# 11_-_Wireless_-_CAN.net
KiCad netlist of a schematic drawn in Altium Designer
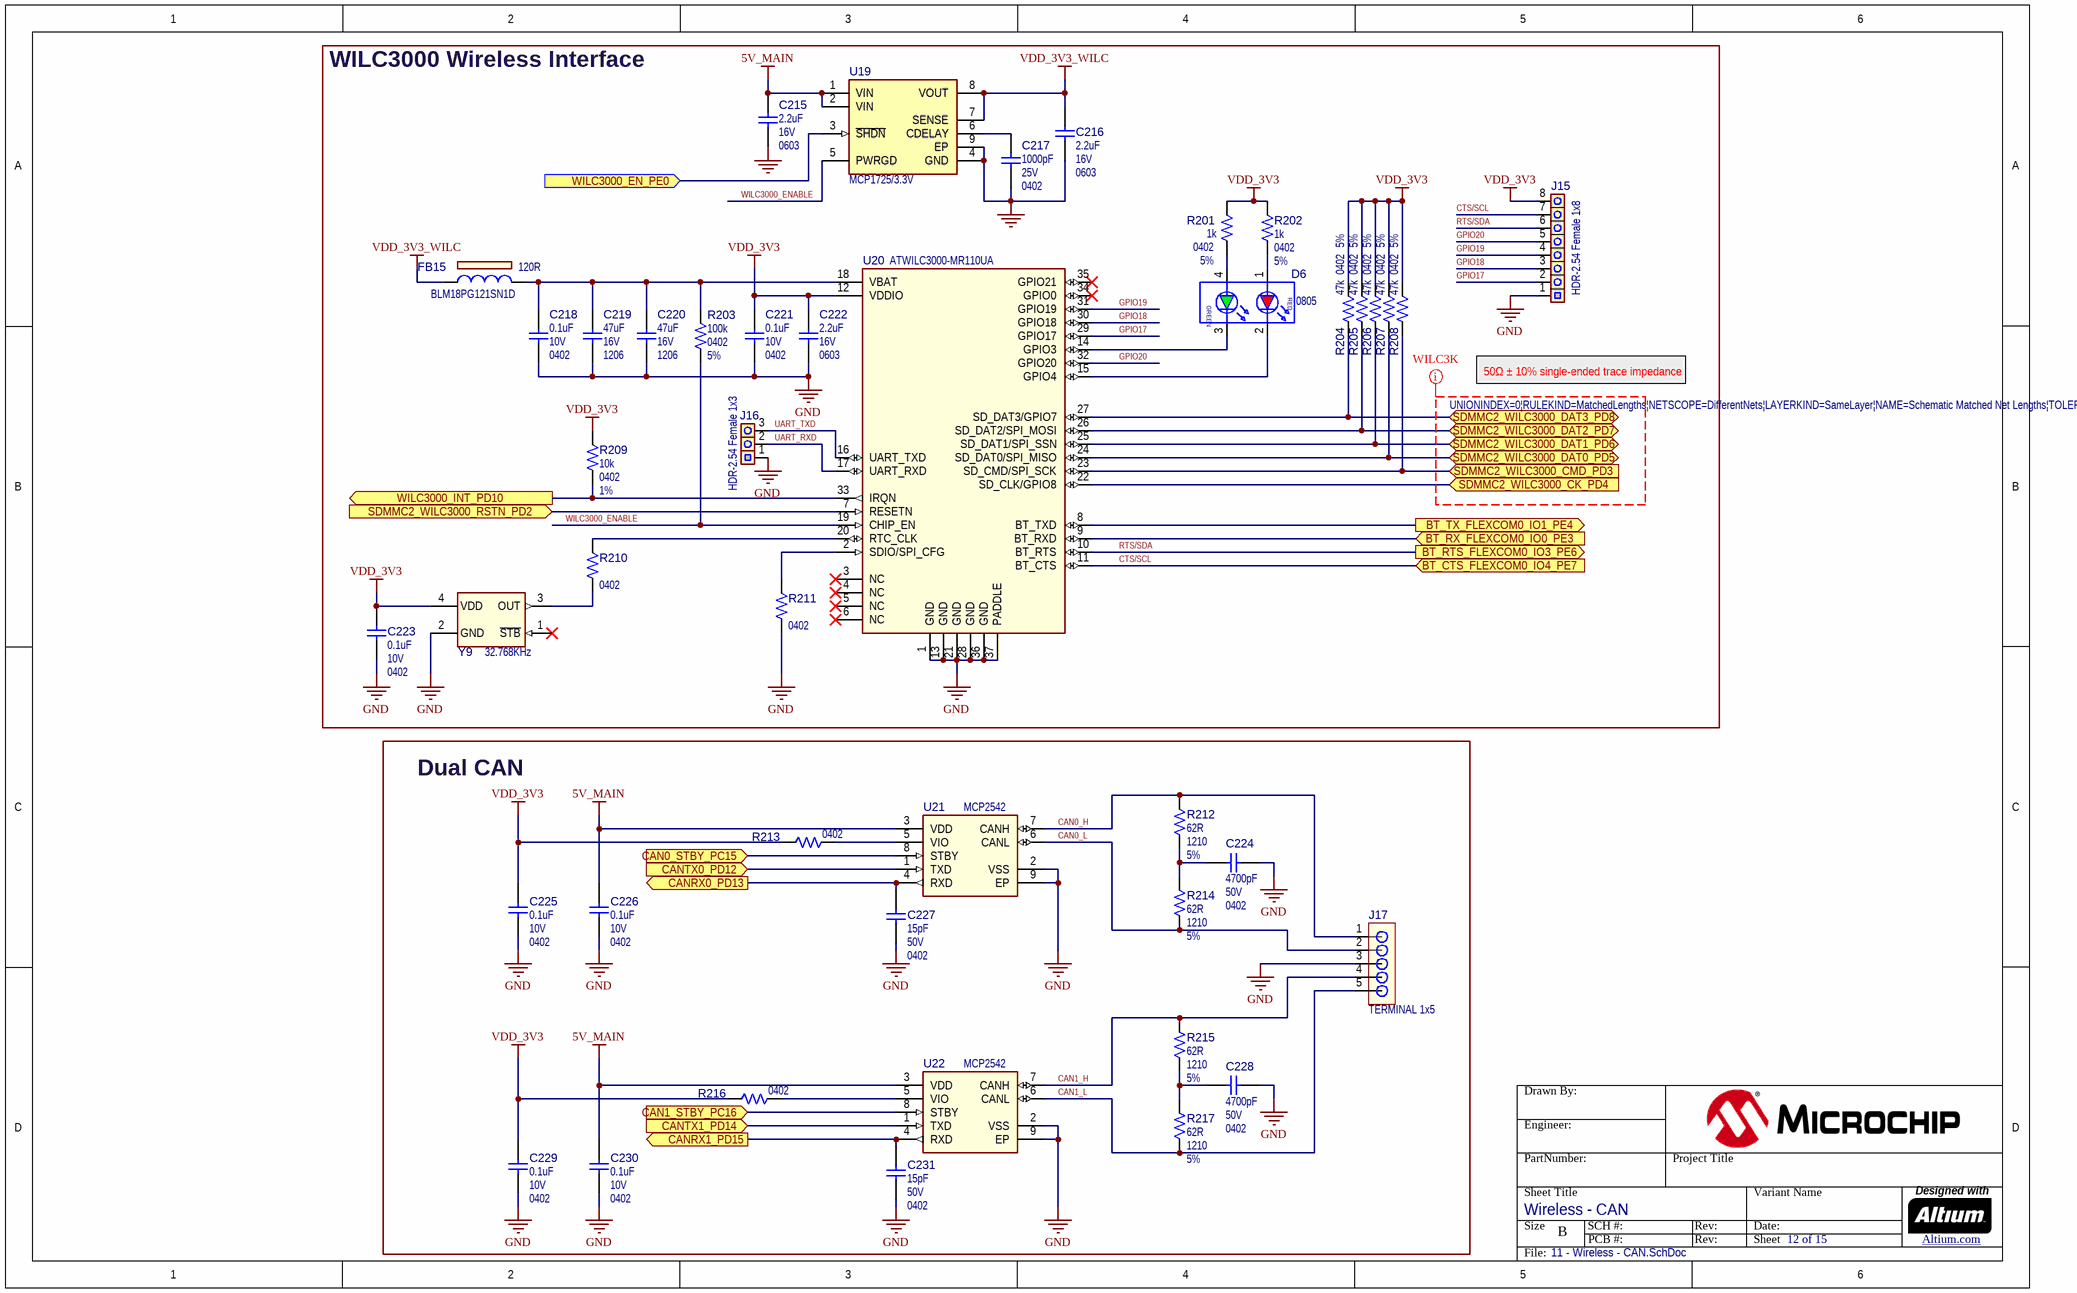
[diagram p0: 11 - Wireless - CAN.SchDoc]

(export (version "E")
  (design (tool "Eeschema 10.0.6"))
  (components
    (comp (ref "C215")
      (value "2.2uF")
      (footprint "CAP_C_0603")
      (description "Capacitor")
      (fields
        (field (name "VOLTAGE") "16V")
        (field (name "PACKAGE") "0603")
        (field (name "TOLERANCE") "10%")
        (field (name "Comment") "Capacitor NP")
      )
      (libsource (lib "MCHP-CDB") (part "Capacitor NP"))
    )
    (comp (ref "C216")
      (value "2.2uF")
      (footprint "CAP_C_0603")
      (description "Capacitor")
      (fields
        (field (name "VOLTAGE") "16V")
        (field (name "PACKAGE") "0603")
        (field (name "TOLERANCE") "10%")
        (field (name "Comment") "Capacitor NP")
      )
      (libsource (lib "MCHP-CDB") (part "Capacitor NP"))
    )
    (comp (ref "C217")
      (value "1000pF")
      (footprint "CAP_C_0402")
      (fields
        (field (name "VOLTAGE") "25V")
        (field (name "PACKAGE") "0402")
        (field (name "TOLERANCE") "10%")
        (field (name "Comment") "Capacitor NP")
        (field (name "OWNER") "Dragos Danaila")
      )
      (libsource (lib "") (part "Capacitor NP_1"))
    )
    (comp (ref "C218")
      (value "0.1uF")
      (footprint "CAP_C_0402")
      (description "Capacitor")
      (fields
        (field (name "VOLTAGE") "10V")
        (field (name "PACKAGE") "0402")
        (field (name "TOLERANCE") "10%")
        (field (name "Comment") "Capacitor NP")
        (field (name "OWNER") "Tad Ahlvers")
      )
      (libsource (lib "MCHP-CDB") (part "Capacitor NP"))
    )
    (comp (ref "C219")
      (value "47uF")
      (footprint "CAP_C_1206")
      (description "Capacitor")
      (fields
        (field (name "VOLTAGE") "16V")
        (field (name "PACKAGE") "1206")
        (field (name "TOLERANCE") "20%")
        (field (name "Comment") "Capacitor NP")
        (field (name "OWNER") "Bogdan Popescu")
      )
      (libsource (lib "MCHP-CDB") (part "Capacitor NP"))
    )
    (comp (ref "C220")
      (value "47uF")
      (footprint "CAP_C_1206")
      (description "Capacitor")
      (fields
        (field (name "VOLTAGE") "16V")
        (field (name "PACKAGE") "1206")
        (field (name "TOLERANCE") "20%")
        (field (name "Comment") "Capacitor NP")
        (field (name "OWNER") "Bogdan Popescu")
      )
      (libsource (lib "MCHP-CDB") (part "Capacitor NP"))
    )
    (comp (ref "C221")
      (value "0.1uF")
      (footprint "CAP_C_0402")
      (description "Capacitor")
      (fields
        (field (name "VOLTAGE") "10V")
        (field (name "PACKAGE") "0402")
        (field (name "TOLERANCE") "10%")
        (field (name "Comment") "Capacitor NP")
        (field (name "OWNER") "Tad Ahlvers")
      )
      (libsource (lib "MCHP-CDB") (part "Capacitor NP"))
    )
    (comp (ref "C222")
      (value "2.2uF")
      (footprint "CAP_C_0603")
      (description "Capacitor")
      (fields
        (field (name "VOLTAGE") "16V")
        (field (name "PACKAGE") "0603")
        (field (name "TOLERANCE") "10%")
        (field (name "Comment") "Capacitor NP")
      )
      (libsource (lib "MCHP-CDB") (part "Capacitor NP"))
    )
    (comp (ref "C223")
      (value "0.1uF")
      (footprint "CAP_C_0402")
      (description "Capacitor")
      (fields
        (field (name "VOLTAGE") "10V")
        (field (name "PACKAGE") "0402")
        (field (name "TOLERANCE") "10%")
        (field (name "Comment") "Capacitor NP")
        (field (name "OWNER") "Tad Ahlvers")
      )
      (libsource (lib "MCHP-CDB") (part "Capacitor NP"))
    )
    (comp (ref "C224")
      (value "4700pF")
      (footprint "CAP_C_0402")
      (description "Capacitor")
      (fields
        (field (name "VOLTAGE") "50V")
        (field (name "PACKAGE") "0402")
        (field (name "TOLERANCE") "10%")
        (field (name "Comment") "Capacitor NP")
        (field (name "OWNER") "Gabor Bihari")
      )
      (libsource (lib "MCHP-CDB") (part "Capacitor NP"))
    )
    (comp (ref "C225")
      (value "0.1uF")
      (footprint "CAP_C_0402")
      (description "Capacitor")
      (fields
        (field (name "VOLTAGE") "10V")
        (field (name "PACKAGE") "0402")
        (field (name "TOLERANCE") "10%")
        (field (name "Comment") "Capacitor NP")
        (field (name "OWNER") "Tad Ahlvers")
      )
      (libsource (lib "MCHP-CDB") (part "Capacitor NP"))
    )
    (comp (ref "C226")
      (value "0.1uF")
      (footprint "CAP_C_0402")
      (description "Capacitor")
      (fields
        (field (name "VOLTAGE") "10V")
        (field (name "PACKAGE") "0402")
        (field (name "TOLERANCE") "10%")
        (field (name "Comment") "Capacitor NP")
        (field (name "OWNER") "Tad Ahlvers")
      )
      (libsource (lib "MCHP-CDB") (part "Capacitor NP"))
    )
    (comp (ref "C227")
      (value "15pF")
      (footprint "CAP_C_0402")
      (fields
        (field (name "VOLTAGE") "50V")
        (field (name "PACKAGE") "0402")
        (field (name "TOLERANCE") "5%")
        (field (name "Comment") "Capacitor NP")
        (field (name "OWNER") "Dragos Danaila")
      )
      (libsource (lib "") (part "Capacitor NP_1"))
    )
    (comp (ref "C228")
      (value "4700pF")
      (footprint "CAP_C_0402")
      (description "Capacitor")
      (fields
        (field (name "VOLTAGE") "50V")
        (field (name "PACKAGE") "0402")
        (field (name "TOLERANCE") "10%")
        (field (name "Comment") "Capacitor NP")
        (field (name "OWNER") "Gabor Bihari")
      )
      (libsource (lib "MCHP-CDB") (part "Capacitor NP"))
    )
    (comp (ref "C229")
      (value "0.1uF")
      (footprint "CAP_C_0402")
      (description "Capacitor")
      (fields
        (field (name "VOLTAGE") "10V")
        (field (name "PACKAGE") "0402")
        (field (name "TOLERANCE") "10%")
        (field (name "Comment") "Capacitor NP")
        (field (name "OWNER") "Tad Ahlvers")
      )
      (libsource (lib "MCHP-CDB") (part "Capacitor NP"))
    )
    (comp (ref "C230")
      (value "0.1uF")
      (footprint "CAP_C_0402")
      (description "Capacitor")
      (fields
        (field (name "VOLTAGE") "10V")
        (field (name "PACKAGE") "0402")
        (field (name "TOLERANCE") "10%")
        (field (name "Comment") "Capacitor NP")
        (field (name "OWNER") "Tad Ahlvers")
      )
      (libsource (lib "MCHP-CDB") (part "Capacitor NP"))
    )
    (comp (ref "C231")
      (value "15pF")
      (footprint "CAP_C_0402")
      (fields
        (field (name "VOLTAGE") "50V")
        (field (name "PACKAGE") "0402")
        (field (name "TOLERANCE") "5%")
        (field (name "Comment") "Capacitor NP")
        (field (name "OWNER") "Dragos Danaila")
      )
      (libsource (lib "") (part "Capacitor NP_1"))
    )
    (comp (ref "D6")
      (value "LED DUAL 4 pin")
      (footprint "LED_DUAL_SMD_2x1.25mm")
      (description "LED")
      (fields
        (field (name "PACKAGE") "0805")
        (field (name "POWER") "75mW")
        (field (name "OWNER") "Bogdan P (M91398)")
      )
      (libsource (lib "MCHP-CDB") (part "LED DUAL 4 pin"))
    )
    (comp (ref "FB15")
      (value "120R")
      (footprint "IND_C_0603")
      (fields
        (field (name "MANUFACTURER PART NUMBER 1") "BLM18PG121SN1D")
        (field (name "Comment") "Ferrite Bead")
        (field (name "OWNER") "Petnarong Chaijaroong")
      )
      (libsource (lib "MCHP-CDB") (part "Ferrite Bead"))
    )
    (comp (ref "J15")
      (value "HDR-2.54 Female 1x8")
      (footprint "HDR_F_2.54_1X8")
      (description "CON HDR-2.54 Female 1x8 Gold TH")
      (fields (field (name "Comment") "Header 1x8") (field (name "OWNER") "Jamus Griego"))
      (libsource (lib "MCHP-CDB") (part "Header 1x8"))
    )
    (comp (ref "J16")
      (value "HDR-2.54 Female 1x3")
      (footprint "HDR_F_2.54_1x3")
      (fields (field (name "Comment") "Header 1x3") (field (name "OWNER") "Md Khan"))
      (libsource (lib "MCHP-CDB") (part "Header 1x3"))
    )
    (comp (ref "J17")
      (value "TERMINAL 1x5")
      (footprint "CON_TERMINAL_3.81_1x5_TH_RA_PHO_1727049")
      (fields
        (field (name "VOLTAGE") "300")
        (field (name "Comment") "Header 1x5")
        (field (name "OWNER") "Ciprian Abramov")
      )
      (libsource (lib "MCHP-CDB") (part "CON TERM BLK 1x5 TH Mount"))
    )
    (comp (ref "R201")
      (value "1k")
      (footprint "RES_C_0402")
      (description "Resistor")
      (fields
        (field (name "PACKAGE") "0402")
        (field (name "TOLERANCE") "5%")
        (field (name "VOLTAGE") "50V")
        (field (name "POWER") "1/16W")
        (field (name "OWNER") "Tad Ahlvers")
      )
      (libsource (lib "MCHP-CDB") (part "Resistor"))
    )
    (comp (ref "R202")
      (value "1k")
      (footprint "RES_C_0402")
      (description "Resistor")
      (fields
        (field (name "PACKAGE") "0402")
        (field (name "TOLERANCE") "5%")
        (field (name "VOLTAGE") "50V")
        (field (name "POWER") "1/16W")
        (field (name "OWNER") "Tad Ahlvers")
      )
      (libsource (lib "MCHP-CDB") (part "Resistor"))
    )
    (comp (ref "R203")
      (value "100k")
      (footprint "RES_C_0402")
      (description "Resistor")
      (fields
        (field (name "PACKAGE") "0402")
        (field (name "TOLERANCE") "5%")
        (field (name "POWER") "1/10W")
        (field (name "VOLTAGE") "50V")
      )
      (libsource (lib "MCHP-CDB") (part "Resistor"))
    )
    (comp (ref "R204")
      (value "47k")
      (footprint "RES_C_0402")
      (description "Resistor")
      (fields
        (field (name "PACKAGE") "0402")
        (field (name "TOLERANCE") "5%")
        (field (name "POWER") "1/10W")
        (field (name "VOLTAGE") "50V")
        (field (name "OWNER") "Tad Ahlvers")
      )
      (libsource (lib "MCHP-CDB") (part "Resistor"))
    )
    (comp (ref "R205")
      (value "47k")
      (footprint "RES_C_0402")
      (description "Resistor")
      (fields
        (field (name "PACKAGE") "0402")
        (field (name "TOLERANCE") "5%")
        (field (name "POWER") "1/10W")
        (field (name "VOLTAGE") "50V")
        (field (name "OWNER") "Tad Ahlvers")
      )
      (libsource (lib "MCHP-CDB") (part "Resistor"))
    )
    (comp (ref "R206")
      (value "47k")
      (footprint "RES_C_0402")
      (description "Resistor")
      (fields
        (field (name "PACKAGE") "0402")
        (field (name "TOLERANCE") "5%")
        (field (name "POWER") "1/10W")
        (field (name "VOLTAGE") "50V")
        (field (name "OWNER") "Tad Ahlvers")
      )
      (libsource (lib "MCHP-CDB") (part "Resistor"))
    )
    (comp (ref "R207")
      (value "47k")
      (footprint "RES_C_0402")
      (description "Resistor")
      (fields
        (field (name "PACKAGE") "0402")
        (field (name "TOLERANCE") "5%")
        (field (name "POWER") "1/10W")
        (field (name "VOLTAGE") "50V")
        (field (name "OWNER") "Tad Ahlvers")
      )
      (libsource (lib "MCHP-CDB") (part "Resistor"))
    )
    (comp (ref "R208")
      (value "47k")
      (footprint "RES_C_0402")
      (description "Resistor")
      (fields
        (field (name "PACKAGE") "0402")
        (field (name "TOLERANCE") "5%")
        (field (name "POWER") "1/10W")
        (field (name "VOLTAGE") "50V")
        (field (name "OWNER") "Tad Ahlvers")
      )
      (libsource (lib "MCHP-CDB") (part "Resistor"))
    )
    (comp (ref "R209")
      (value "10k")
      (footprint "RES_C_0402")
      (description "Resistor")
      (fields
        (field (name "PACKAGE") "0402")
        (field (name "TOLERANCE") "1%")
        (field (name "VOLTAGE") "50V")
        (field (name "POWER") "1/10W")
        (field (name "OWNER") "Brent Lanphear")
      )
      (libsource (lib "MCHP-CDB") (part "Resistor"))
    )
    (comp (ref "R210")
      (value "Resistor")
      (footprint "RES_C_0402")
      (fields
        (field (name "PACKAGE") "0402")
        (field (name "POWER") "1/16W")
        (field (name "VOLTAGE") "50V")
        (field (name "OWNER") "Dragos Danaila")
      )
      (libsource (lib "MCHP-CDB") (part "Resistor"))
    )
    (comp (ref "R211")
      (value "Resistor")
      (footprint "RES_C_0402")
      (fields
        (field (name "PACKAGE") "0402")
        (field (name "POWER") "1/16W")
        (field (name "VOLTAGE") "50V")
        (field (name "OWNER") "Dragos Danaila")
      )
      (libsource (lib "MCHP-CDB") (part "Resistor"))
    )
    (comp (ref "R212")
      (value "62R")
      (footprint "RES_C_1210")
      (description "Resistor")
      (fields
        (field (name "PACKAGE") "1210")
        (field (name "TOLERANCE") "5%")
        (field (name "VOLTAGE") "200V")
        (field (name "POWER") "1/2W")
        (field (name "OWNER") "Dragos Danaila")
      )
      (libsource (lib "MCHP-CDB") (part "Resistor"))
    )
    (comp (ref "R213")
      (value "Resistor")
      (footprint "RES_C_0402")
      (fields
        (field (name "PACKAGE") "0402")
        (field (name "POWER") "1/16W")
        (field (name "VOLTAGE") "50V")
        (field (name "OWNER") "Dragos Danaila")
      )
      (libsource (lib "MCHP-CDB") (part "Resistor"))
    )
    (comp (ref "R214")
      (value "62R")
      (footprint "RES_C_1210")
      (description "Resistor")
      (fields
        (field (name "PACKAGE") "1210")
        (field (name "TOLERANCE") "5%")
        (field (name "VOLTAGE") "200V")
        (field (name "POWER") "1/2W")
        (field (name "OWNER") "Dragos Danaila")
      )
      (libsource (lib "MCHP-CDB") (part "Resistor"))
    )
    (comp (ref "R215")
      (value "62R")
      (footprint "RES_C_1210")
      (description "Resistor")
      (fields
        (field (name "PACKAGE") "1210")
        (field (name "TOLERANCE") "5%")
        (field (name "VOLTAGE") "200V")
        (field (name "POWER") "1/2W")
        (field (name "OWNER") "Dragos Danaila")
      )
      (libsource (lib "MCHP-CDB") (part "Resistor"))
    )
    (comp (ref "R216")
      (value "Resistor")
      (footprint "RES_C_0402")
      (fields
        (field (name "PACKAGE") "0402")
        (field (name "POWER") "1/16W")
        (field (name "VOLTAGE") "50V")
        (field (name "OWNER") "Dragos Danaila")
      )
      (libsource (lib "MCHP-CDB") (part "Resistor"))
    )
    (comp (ref "R217")
      (value "62R")
      (footprint "RES_C_1210")
      (description "Resistor")
      (fields
        (field (name "PACKAGE") "1210")
        (field (name "TOLERANCE") "5%")
        (field (name "VOLTAGE") "200V")
        (field (name "POWER") "1/2W")
        (field (name "OWNER") "Dragos Danaila")
      )
      (libsource (lib "MCHP-CDB") (part "Resistor"))
    )
    (comp (ref "U19")
      (value "MCP1725/3.3V")
      (footprint "DFN-8_2x3")
      (description "LDO")
      (fields (field (name "Comment") "MCP172X FIX DFN-8"))
      (libsource (lib "MCHP-CDB") (part "MCP172X FIX DFN-8"))
    )
    (comp (ref "U20")
      (value "ATWILC3000-MR110UA")
      (footprint "MODULE ATWILC3000-MR110CA")
      (fields (field (name "Comment") "MODULE ATWILC3000-MR110CA") (field (name "OWNER") "Ilie Galan"))
      (libsource (lib "MCHP-CDB") (part "MODULE ATWILC3000-MR110CA"))
    )
    (comp (ref "U21")
      (value "MCP2542")
      (footprint "DFN-8_3x3_EP2.4X1.55")
      (fields (field (name "Comment") "MCP2542 DFN-8") (field (name "OWNER") "Ilie Galan"))
      (libsource (lib "MCHP-CDB") (part "MCP2542 DFN-8"))
    )
    (comp (ref "U22")
      (value "MCP2542")
      (footprint "DFN-8_3x3_EP2.4X1.55")
      (fields (field (name "Comment") "MCP2542 DFN-8") (field (name "OWNER") "Ilie Galan"))
      (libsource (lib "MCHP-CDB") (part "MCP2542 DFN-8"))
    )
    (comp (ref "Y9")
      (value "32.768KHz")
      (footprint "DFN-4_2x1.6")
      (fields (field (name "Comment") "DSC60xx DFN-4_LGA-4") (field (name "OWNER") "Ciprian Abramov"))
      (libsource (lib "MCHP-CDB") (part "DSC60xx DFN-4_LGA-4"))
    )
  )
  (nets
    (net (code "1") (name "/BT_RX_FLEXCOM0_IO0_PE3") (class "Default")
      (node (ref "U20") (pin "9") (pinfunction "BT_RXD_9") (pintype "bidirectional"))
    )
    (net (code "2") (name "/BT_TX_FLEXCOM0_IO1_PE4") (class "Default")
      (node (ref "U20") (pin "8") (pinfunction "BT_TXD_8") (pintype "bidirectional"))
    )
    (net (code "3") (name "/CAN0_H") (class "Default")
      (node (ref "J17") (pin "1") (pinfunction "1_1") (pintype "passive"))
      (node (ref "R212") (pin "2") (pinfunction "2_2") (pintype "passive"))
      (node (ref "U21") (pin "7") (pinfunction "CANH_7") (pintype "bidirectional"))
    )
    (net (code "4") (name "/CAN0_L") (class "Default")
      (node (ref "J17") (pin "2") (pinfunction "2_2") (pintype "passive"))
      (node (ref "R214") (pin "1") (pinfunction "1_1") (pintype "passive"))
      (node (ref "U21") (pin "6") (pinfunction "CANL_6") (pintype "bidirectional"))
    )
    (net (code "5") (name "/CAN0_STBY_PC15") (class "Default")
      (node (ref "U21") (pin "8") (pinfunction "STBY_8") (pintype "input"))
    )
    (net (code "6") (name "/CAN1_H") (class "Default")
      (node (ref "J17") (pin "4") (pinfunction "4_4") (pintype "passive"))
      (node (ref "R215") (pin "2") (pinfunction "2_2") (pintype "passive"))
      (node (ref "U22") (pin "7") (pinfunction "CANH_7") (pintype "bidirectional"))
    )
    (net (code "7") (name "/CAN1_L") (class "Default")
      (node (ref "J17") (pin "5") (pinfunction "5_5") (pintype "passive"))
      (node (ref "R217") (pin "1") (pinfunction "1_1") (pintype "passive"))
      (node (ref "U22") (pin "6") (pinfunction "CANL_6") (pintype "bidirectional"))
    )
    (net (code "8") (name "/CAN1_STBY_PC16") (class "Default")
      (node (ref "U22") (pin "8") (pinfunction "STBY_8") (pintype "input"))
    )
    (net (code "9") (name "/CANRX0_PD13") (class "Default")
      (node (ref "C227") (pin "2") (pinfunction "2_2") (pintype "passive"))
      (node (ref "U21") (pin "4") (pinfunction "RXD_4") (pintype "output"))
    )
    (net (code "10") (name "/CANRX1_PD15") (class "Default")
      (node (ref "C231") (pin "2") (pinfunction "2_2") (pintype "passive"))
      (node (ref "U22") (pin "4") (pinfunction "RXD_4") (pintype "output"))
    )
    (net (code "11") (name "/CANTX0_PD12") (class "Default")
      (node (ref "U21") (pin "1") (pinfunction "TXD_1") (pintype "input"))
    )
    (net (code "12") (name "/CANTX1_PD14") (class "Default")
      (node (ref "U22") (pin "1") (pinfunction "TXD_1") (pintype "input"))
    )
    (net (code "13") (name "/CTS{slash}SCL") (class "Default")
      (node (ref "J15") (pin "7") (pinfunction "7_7") (pintype "passive"))
      (node (ref "U20") (pin "11") (pinfunction "BT_CTS_11") (pintype "bidirectional"))
    )
    (net (code "14") (name "/GPIO17") (class "Default")
      (node (ref "J15") (pin "2") (pinfunction "2_2") (pintype "passive"))
      (node (ref "U20") (pin "29") (pinfunction "GPIO17_29") (pintype "bidirectional"))
    )
    (net (code "15") (name "/GPIO18") (class "Default")
      (node (ref "J15") (pin "3") (pinfunction "3_3") (pintype "passive"))
      (node (ref "U20") (pin "30") (pinfunction "GPIO18_30") (pintype "bidirectional"))
    )
    (net (code "16") (name "/GPIO19") (class "Default")
      (node (ref "J15") (pin "4") (pinfunction "4_4") (pintype "passive"))
      (node (ref "U20") (pin "31") (pinfunction "GPIO19_31") (pintype "bidirectional"))
    )
    (net (code "17") (name "/GPIO20") (class "Default")
      (node (ref "J15") (pin "5") (pinfunction "5_5") (pintype "passive"))
      (node (ref "U20") (pin "32") (pinfunction "GPIO20_32") (pintype "bidirectional"))
    )
    (net (code "18") (name "/RTS{slash}SDA") (class "Default")
      (node (ref "J15") (pin "6") (pinfunction "6_6") (pintype "passive"))
      (node (ref "U20") (pin "10") (pinfunction "BT_RTS_10") (pintype "bidirectional"))
    )
    (net (code "19") (name "/SDMMC2_WILC3000_CK_PD4") (class "Default")
      (node (ref "U20") (pin "22") (pinfunction "SD_CLK/GPIO8_22") (pintype "bidirectional"))
    )
    (net (code "20") (name "/SDMMC2_WILC3000_CMD_PD3") (class "Default")
      (node (ref "R208") (pin "1") (pinfunction "1_1") (pintype "passive"))
      (node (ref "U20") (pin "23") (pinfunction "SD_CMD/SPI_SCK_23") (pintype "bidirectional"))
    )
    (net (code "21") (name "/SDMMC2_WILC3000_DAT0_PD5") (class "Default")
      (node (ref "R207") (pin "1") (pinfunction "1_1") (pintype "passive"))
      (node (ref "U20") (pin "24") (pinfunction "SD_DAT0/SPI_MISO_24") (pintype "bidirectional"))
    )
    (net (code "22") (name "/SDMMC2_WILC3000_DAT1_PD6") (class "Default")
      (node (ref "R206") (pin "1") (pinfunction "1_1") (pintype "passive"))
      (node (ref "U20") (pin "25") (pinfunction "SD_DAT1/SPI_SSN_25") (pintype "bidirectional"))
    )
    (net (code "23") (name "/SDMMC2_WILC3000_DAT2_PD7") (class "Default")
      (node (ref "R205") (pin "1") (pinfunction "1_1") (pintype "passive"))
      (node (ref "U20") (pin "26") (pinfunction "SD_DAT2/SPI_MOSI_26") (pintype "bidirectional"))
    )
    (net (code "24") (name "/SDMMC2_WILC3000_DAT3_PD8") (class "Default")
      (node (ref "R204") (pin "1") (pinfunction "1_1") (pintype "passive"))
      (node (ref "U20") (pin "27") (pinfunction "SD_DAT3/GPIO7_27") (pintype "bidirectional"))
    )
    (net (code "25") (name "/SDMMC2_WILC3000_RSTN_PD2") (class "Default")
      (node (ref "U20") (pin "7") (pinfunction "RESETN_7") (pintype "input"))
    )
    (net (code "26") (name "/UART_RXD") (class "Default")
      (node (ref "J16") (pin "2") (pinfunction "2_2") (pintype "passive"))
      (node (ref "U20") (pin "17") (pinfunction "UART_RXD_17") (pintype "bidirectional"))
    )
    (net (code "27") (name "/UART_TXD") (class "Default")
      (node (ref "J16") (pin "3") (pinfunction "3_3") (pintype "passive"))
      (node (ref "U20") (pin "16") (pinfunction "UART_TXD_16") (pintype "bidirectional"))
    )
    (net (code "28") (name "/WILC3000_ENABLE") (class "Default")
      (node (ref "R203") (pin "1") (pinfunction "1_1") (pintype "passive"))
      (node (ref "U19") (pin "5") (pinfunction "PWRGD_5") (pintype "open_collector"))
      (node (ref "U20") (pin "19") (pinfunction "CHIP_EN_19") (pintype "input"))
    )
    (net (code "29") (name "/WILC3000_EN_PE0") (class "Default")
      (node (ref "U19") (pin "3") (pinfunction "~{SHDN}_3") (pintype "input"))
    )
    (net (code "30") (name "/WILC3000_INT_PD10") (class "Default")
      (node (ref "R209") (pin "1") (pinfunction "1_1") (pintype "passive"))
      (node (ref "U20") (pin "33") (pinfunction "IRQN_33") (pintype "output"))
    )
    (net (code "31") (name "5V_MAIN") (class "Default")
      (node (ref "C215") (pin "1") (pinfunction "1_1") (pintype "passive"))
      (node (ref "C226") (pin "1") (pinfunction "1_1") (pintype "passive"))
      (node (ref "C230") (pin "1") (pinfunction "1_1") (pintype "passive"))
      (node (ref "U19") (pin "1") (pinfunction "VIN_1") (pintype "power_in"))
      (node (ref "U19") (pin "2") (pinfunction "VIN_2") (pintype "power_in"))
      (node (ref "U21") (pin "3") (pinfunction "VDD_3") (pintype "power_in"))
      (node (ref "U22") (pin "3") (pinfunction "VDD_3") (pintype "power_in"))
    )
    (net (code "32") (name "GND") (class "Default")
      (node (ref "C215") (pin "2") (pinfunction "2_2") (pintype "passive"))
      (node (ref "C216") (pin "1") (pinfunction "1_1") (pintype "passive"))
      (node (ref "C217") (pin "1") (pinfunction "1_1") (pintype "passive"))
      (node (ref "C218") (pin "2") (pinfunction "2_2") (pintype "passive"))
      (node (ref "C219") (pin "2") (pinfunction "2_2") (pintype "passive"))
      (node (ref "C220") (pin "2") (pinfunction "2_2") (pintype "passive"))
      (node (ref "C221") (pin "2") (pinfunction "2_2") (pintype "passive"))
      (node (ref "C222") (pin "1") (pinfunction "1_1") (pintype "passive"))
      (node (ref "C223") (pin "2") (pinfunction "2_2") (pintype "passive"))
      (node (ref "C224") (pin "1") (pinfunction "1_1") (pintype "passive"))
      (node (ref "C225") (pin "2") (pinfunction "2_2") (pintype "passive"))
      (node (ref "C226") (pin "2") (pinfunction "2_2") (pintype "passive"))
      (node (ref "C227") (pin "1") (pinfunction "1_1") (pintype "passive"))
      (node (ref "C228") (pin "1") (pinfunction "1_1") (pintype "passive"))
      (node (ref "C229") (pin "2") (pinfunction "2_2") (pintype "passive"))
      (node (ref "C230") (pin "2") (pinfunction "2_2") (pintype "passive"))
      (node (ref "C231") (pin "1") (pinfunction "1_1") (pintype "passive"))
      (node (ref "J15") (pin "1") (pinfunction "1_1") (pintype "passive"))
      (node (ref "J16") (pin "1") (pinfunction "1_1") (pintype "passive"))
      (node (ref "J17") (pin "3") (pinfunction "3_3") (pintype "passive"))
      (node (ref "R211") (pin "2") (pinfunction "2_2") (pintype "passive"))
      (node (ref "U19") (pin "4") (pinfunction "GND_4") (pintype "power_in"))
      (node (ref "U19") (pin "9") (pinfunction "EP_9") (pintype "passive"))
      (node (ref "U20") (pin "1") (pinfunction "GND_1") (pintype "power_in"))
      (node (ref "U20") (pin "13") (pinfunction "GND_13") (pintype "power_in"))
      (node (ref "U20") (pin "21") (pinfunction "GND_21") (pintype "power_in"))
      (node (ref "U20") (pin "28") (pinfunction "GND_28") (pintype "power_in"))
      (node (ref "U20") (pin "36") (pinfunction "GND_36") (pintype "power_in"))
      (node (ref "U20") (pin "37") (pinfunction "PADDLE_37") (pintype "power_in"))
      (node (ref "U21") (pin "2") (pinfunction "VSS_2") (pintype "power_in"))
      (node (ref "U21") (pin "9") (pinfunction "EP_9") (pintype "passive"))
      (node (ref "U22") (pin "2") (pinfunction "VSS_2") (pintype "power_in"))
      (node (ref "U22") (pin "9") (pinfunction "EP_9") (pintype "passive"))
      (node (ref "Y9") (pin "2") (pinfunction "GND_2") (pintype "power_in"))
    )
    (net (code "33") (name "Net-(C224-Pad2)") (class "Default")
      (node (ref "C224") (pin "2") (pinfunction "2_2") (pintype "passive"))
      (node (ref "R212") (pin "1") (pinfunction "1_1") (pintype "passive"))
      (node (ref "R214") (pin "2") (pinfunction "2_2") (pintype "passive"))
    )
    (net (code "34") (name "Net-(C228-Pad2)") (class "Default")
      (node (ref "C228") (pin "2") (pinfunction "2_2") (pintype "passive"))
      (node (ref "R215") (pin "1") (pinfunction "1_1") (pintype "passive"))
      (node (ref "R217") (pin "2") (pinfunction "2_2") (pintype "passive"))
    )
    (net (code "35") (name "Net-(D6-A1)") (class "Default")
      (node (ref "D6") (pin "1") (pinfunction "A1_1") (pintype "passive"))
      (node (ref "R202") (pin "1") (pinfunction "1_1") (pintype "passive"))
    )
    (net (code "36") (name "Net-(D6-A2)") (class "Default")
      (node (ref "D6") (pin "4") (pinfunction "A2_4") (pintype "passive"))
      (node (ref "R201") (pin "1") (pinfunction "1_1") (pintype "passive"))
    )
    (net (code "37") (name "Net-(D6-K1)") (class "Default")
      (node (ref "D6") (pin "2") (pinfunction "K1_2") (pintype "passive"))
      (node (ref "U20") (pin "15") (pinfunction "GPIO4_15") (pintype "bidirectional"))
    )
    (net (code "38") (name "Net-(D6-K2)") (class "Default")
      (node (ref "D6") (pin "3") (pinfunction "K2_3") (pintype "passive"))
      (node (ref "U20") (pin "14") (pinfunction "GPIO3_14") (pintype "bidirectional"))
    )
    (net (code "39") (name "Net-(U19-CDELAY)") (class "Default")
      (node (ref "C217") (pin "2") (pinfunction "2_2") (pintype "passive"))
      (node (ref "U19") (pin "6") (pinfunction "CDELAY_6") (pintype "passive"))
    )
    (net (code "40") (name "Net-(U20-RTC_CLK)") (class "Default")
      (node (ref "R210") (pin "1") (pinfunction "1_1") (pintype "passive"))
      (node (ref "U20") (pin "20") (pinfunction "RTC_CLK_20") (pintype "bidirectional"))
    )
    (net (code "41") (name "Net-(U20-SDIO{slash}SPI_CFG)") (class "Default")
      (node (ref "R211") (pin "1") (pinfunction "1_1") (pintype "passive"))
      (node (ref "U20") (pin "2") (pinfunction "SDIO/SPI_CFG_2") (pintype "input"))
    )
    (net (code "42") (name "Net-(U20-VBAT)") (class "Default")
      (node (ref "C218") (pin "1") (pinfunction "1_1") (pintype "passive"))
      (node (ref "C219") (pin "1") (pinfunction "1_1") (pintype "passive"))
      (node (ref "C220") (pin "1") (pinfunction "1_1") (pintype "passive"))
      (node (ref "FB15") (pin "2") (pinfunction "2_2") (pintype "passive"))
      (node (ref "R203") (pin "2") (pinfunction "2_2") (pintype "passive"))
      (node (ref "U20") (pin "18") (pinfunction "VBAT_18") (pintype "power_in"))
    )
    (net (code "43") (name "Net-(U21-VIO)") (class "Default")
      (node (ref "R213") (pin "2") (pinfunction "2_2") (pintype "passive"))
      (node (ref "U21") (pin "5") (pinfunction "VIO_5") (pintype "power_in"))
    )
    (net (code "44") (name "Net-(U22-VIO)") (class "Default")
      (node (ref "R216") (pin "2") (pinfunction "2_2") (pintype "passive"))
      (node (ref "U22") (pin "5") (pinfunction "VIO_5") (pintype "power_in"))
    )
    (net (code "45") (name "Net-(Y9-OUT)") (class "Default")
      (node (ref "R210") (pin "2") (pinfunction "2_2") (pintype "passive"))
      (node (ref "Y9") (pin "3") (pinfunction "OUT_3") (pintype "output"))
    )
    (net (code "46") (name "VDD_3V3") (class "Default")
      (node (ref "C221") (pin "1") (pinfunction "1_1") (pintype "passive"))
      (node (ref "C222") (pin "2") (pinfunction "2_2") (pintype "passive"))
      (node (ref "C223") (pin "1") (pinfunction "1_1") (pintype "passive"))
      (node (ref "C225") (pin "1") (pinfunction "1_1") (pintype "passive"))
      (node (ref "C229") (pin "1") (pinfunction "1_1") (pintype "passive"))
      (node (ref "J15") (pin "8") (pinfunction "8_8") (pintype "passive"))
      (node (ref "R201") (pin "2") (pinfunction "2_2") (pintype "passive"))
      (node (ref "R202") (pin "2") (pinfunction "2_2") (pintype "passive"))
      (node (ref "R204") (pin "2") (pinfunction "2_2") (pintype "passive"))
      (node (ref "R205") (pin "2") (pinfunction "2_2") (pintype "passive"))
      (node (ref "R206") (pin "2") (pinfunction "2_2") (pintype "passive"))
      (node (ref "R207") (pin "2") (pinfunction "2_2") (pintype "passive"))
      (node (ref "R208") (pin "2") (pinfunction "2_2") (pintype "passive"))
      (node (ref "R209") (pin "2") (pinfunction "2_2") (pintype "passive"))
      (node (ref "R213") (pin "1") (pinfunction "1_1") (pintype "passive"))
      (node (ref "R216") (pin "1") (pinfunction "1_1") (pintype "passive"))
      (node (ref "U20") (pin "12") (pinfunction "VDDIO_12") (pintype "power_in"))
      (node (ref "Y9") (pin "4") (pinfunction "VDD_4") (pintype "power_in"))
    )
    (net (code "47") (name "VDD_3V3_WILC") (class "Default")
      (node (ref "C216") (pin "2") (pinfunction "2_2") (pintype "passive"))
      (node (ref "FB15") (pin "1") (pinfunction "1_1") (pintype "passive"))
      (node (ref "U19") (pin "7") (pinfunction "SENSE_7") (pintype "passive"))
      (node (ref "U19") (pin "8") (pinfunction "VOUT_8") (pintype "power_in"))
    )
    (net (code "48") (name "unconnected-(U20-GPIO0-Pad34)") (class "Default")
      (node (ref "U20") (pin "34") (pinfunction "GPIO0_34") (pintype "bidirectional+no_connect"))
    )
    (net (code "49") (name "unconnected-(U20-GPIO21-Pad35)") (class "Default")
      (node (ref "U20") (pin "35") (pinfunction "GPIO21_35") (pintype "bidirectional+no_connect"))
    )
    (net (code "50") (name "unconnected-(U20-NC-Pad3)") (class "Default")
      (node (ref "U20") (pin "3") (pinfunction "NC_3") (pintype "passive+no_connect"))
    )
    (net (code "51") (name "unconnected-(U20-NC-Pad4)") (class "Default")
      (node (ref "U20") (pin "4") (pinfunction "NC_4") (pintype "passive+no_connect"))
    )
    (net (code "52") (name "unconnected-(U20-NC-Pad5)") (class "Default")
      (node (ref "U20") (pin "5") (pinfunction "NC_5") (pintype "passive+no_connect"))
    )
    (net (code "53") (name "unconnected-(U20-NC-Pad6)") (class "Default")
      (node (ref "U20") (pin "6") (pinfunction "NC_6") (pintype "passive+no_connect"))
    )
    (net (code "54") (name "unconnected-(Y9-~{STB}-Pad1)") (class "Default")
      (node (ref "Y9") (pin "1") (pinfunction "~{STB}_1") (pintype "input+no_connect"))
    )
  )
)
